# zeta2rework_lw_v20.net
KiCad netlist of a schematic drawn in EAGLE
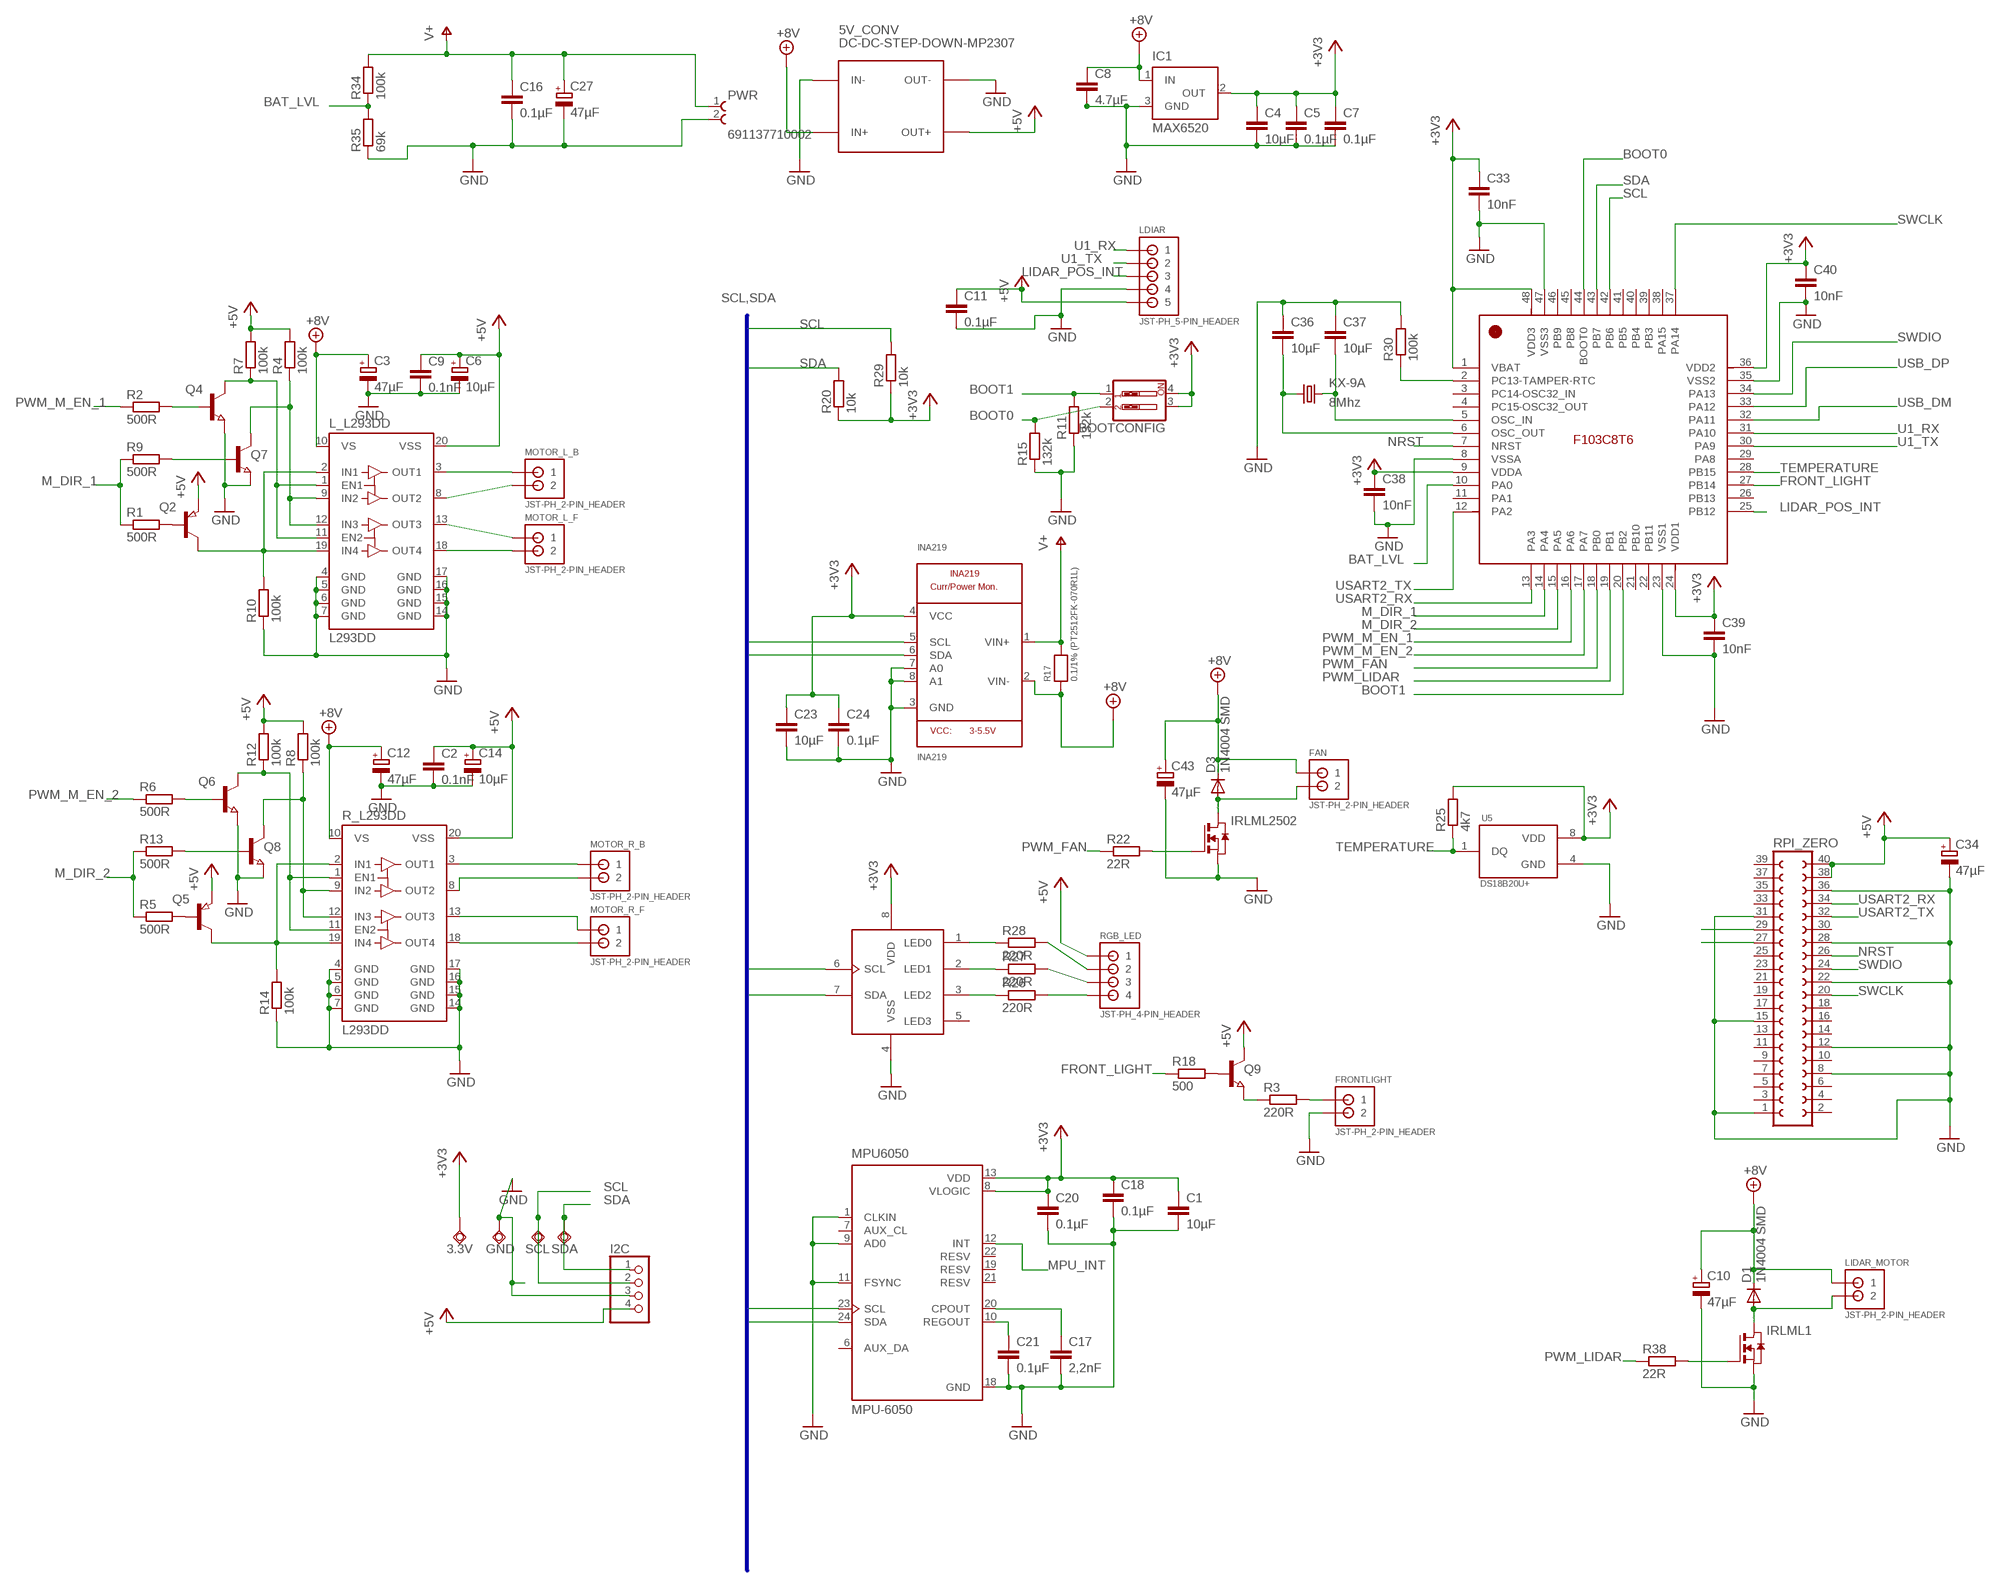
[diagram p0: schematic, sheet 1]

(export (version "E")
  (design (tool "Eeschema 10.0.6"))
  (components
    (comp (ref "3.3V")
      (value "TPSQTP20R")
      (footprint "eagle-import:TP20R")
      (libsource (lib "eagle-import") (part "TPSQTP20R"))
    )
    (comp (ref "5V_CONV")
      (value "DC-DC-STEP-DOWN-MP2307")
      (footprint "eagle-import:DC-DC-STEP-DOWN-MP2307")
      (libsource (lib "eagle-import") (part "DC-DC-STEP-DOWN-MP2307"))
    )
    (comp (ref "BOOTCONFIG")
      (value "SW_DIP-2")
      (footprint "eagle-import:EDG-02")
      (libsource (lib "eagle-import") (part "SW_DIP-2"))
    )
    (comp (ref "C1")
      (value "10µF")
      (footprint "eagle-import:C1206")
      (libsource (lib "eagle-import") (part "C-EUC1206"))
    )
    (comp (ref "C2")
      (value "0.1nF")
      (footprint "eagle-import:C1206")
      (libsource (lib "eagle-import") (part "C-EUC1206"))
    )
    (comp (ref "C3")
      (value "47µF")
      (footprint "eagle-import:UD-4X5,8_NICHICON")
      (libsource (lib "eagle-import") (part "CPOL-EUUD-4X5,8"))
    )
    (comp (ref "C4")
      (value "10µF")
      (footprint "eagle-import:C1206")
      (libsource (lib "eagle-import") (part "C-EUC1206"))
    )
    (comp (ref "C5")
      (value "0.1µF")
      (footprint "eagle-import:C1206")
      (libsource (lib "eagle-import") (part "C-EUC1206"))
    )
    (comp (ref "C6")
      (value "10µF")
      (footprint "eagle-import:UD-4X5,8_NICHICON")
      (libsource (lib "eagle-import") (part "CPOL-EUUD-4X5,8"))
    )
    (comp (ref "C7")
      (value "0.1µF")
      (footprint "eagle-import:C1206")
      (libsource (lib "eagle-import") (part "C-EUC1206"))
    )
    (comp (ref "C8")
      (value "4.7µF")
      (footprint "eagle-import:C1206")
      (libsource (lib "eagle-import") (part "C-EUC1206"))
    )
    (comp (ref "C9")
      (value "0.1nF")
      (footprint "eagle-import:C1206")
      (libsource (lib "eagle-import") (part "C-EUC1206"))
    )
    (comp (ref "C10")
      (value "47µF")
      (footprint "eagle-import:UD-4X5,8_NICHICON")
      (libsource (lib "eagle-import") (part "CPOL-EUUD-4X5,8"))
    )
    (comp (ref "C11")
      (value "0.1µF")
      (footprint "eagle-import:C1206")
      (libsource (lib "eagle-import") (part "C-EUC1206"))
    )
    (comp (ref "C12")
      (value "47µF")
      (footprint "eagle-import:UD-4X5,8_NICHICON")
      (libsource (lib "eagle-import") (part "CPOL-EUUD-4X5,8"))
    )
    (comp (ref "C14")
      (value "10µF")
      (footprint "eagle-import:UD-4X5,8_NICHICON")
      (libsource (lib "eagle-import") (part "CPOL-EUUD-4X5,8"))
    )
    (comp (ref "C16")
      (value "0.1µF")
      (footprint "eagle-import:C1206")
      (libsource (lib "eagle-import") (part "C-EUC1206"))
    )
    (comp (ref "C17")
      (value "2,2nF")
      (footprint "eagle-import:C1206")
      (libsource (lib "eagle-import") (part "C-EUC1206"))
    )
    (comp (ref "C18")
      (value "0.1µF")
      (footprint "eagle-import:C1206")
      (libsource (lib "eagle-import") (part "C-EUC1206"))
    )
    (comp (ref "C20")
      (value "0.1µF")
      (footprint "eagle-import:C1206")
      (libsource (lib "eagle-import") (part "C-EUC1206"))
    )
    (comp (ref "C21")
      (value "0.1µF")
      (footprint "eagle-import:C1206")
      (libsource (lib "eagle-import") (part "C-EUC1206"))
    )
    (comp (ref "C23")
      (value "10µF")
      (footprint "eagle-import:C1206")
      (libsource (lib "eagle-import") (part "C-EUC1206"))
    )
    (comp (ref "C24")
      (value "0.1µF")
      (footprint "eagle-import:C1206")
      (libsource (lib "eagle-import") (part "C-EUC1206"))
    )
    (comp (ref "C27")
      (value "47µF")
      (footprint "eagle-import:UD-4X5,8_NICHICON")
      (libsource (lib "eagle-import") (part "CPOL-EUUD-4X5,8"))
    )
    (comp (ref "C33")
      (value "10nF")
      (footprint "eagle-import:C1206")
      (libsource (lib "eagle-import") (part "C-EUC1206"))
    )
    (comp (ref "C34")
      (value "47µF")
      (footprint "eagle-import:UD-4X5,8_NICHICON")
      (libsource (lib "eagle-import") (part "CPOL-EUUD-4X5,8"))
    )
    (comp (ref "C36")
      (value "10µF")
      (footprint "eagle-import:C1206")
      (libsource (lib "eagle-import") (part "C-EUC1206"))
    )
    (comp (ref "C37")
      (value "10µF")
      (footprint "eagle-import:C1206")
      (libsource (lib "eagle-import") (part "C-EUC1206"))
    )
    (comp (ref "C38")
      (value "10nF")
      (footprint "eagle-import:C1206")
      (libsource (lib "eagle-import") (part "C-EUC1206"))
    )
    (comp (ref "C39")
      (value "10nF")
      (footprint "eagle-import:C1206")
      (libsource (lib "eagle-import") (part "C-EUC1206"))
    )
    (comp (ref "C40")
      (value "10nF")
      (footprint "eagle-import:C1206")
      (libsource (lib "eagle-import") (part "C-EUC1206"))
    )
    (comp (ref "C43")
      (value "47µF")
      (footprint "eagle-import:UD-4X5,8_NICHICON")
      (libsource (lib "eagle-import") (part "CPOL-EUUD-4X5,8"))
    )
    (comp (ref "D1")
      (value "1N4004 SMD")
      (footprint "eagle-import:DO214AC")
      (libsource (lib "eagle-import") (part "DIODE-DO214AC"))
    )
    (comp (ref "D3")
      (value "1N4004 SMD")
      (footprint "eagle-import:DO214AC")
      (libsource (lib "eagle-import") (part "DIODE-DO214AC"))
    )
    (comp (ref "FAN")
      (value "JST-PH_2-PIN_HEADER")
      (footprint "eagle-import:JST_B2B-PH_HEADER")
      (libsource (lib "eagle-import") (part "JST-PH_2-PIN_HEADER"))
    )
    (comp (ref "FRONTLIGHT")
      (value "JST-PH_2-PIN_HEADER")
      (footprint "eagle-import:JST_B2B-PH_HEADER")
      (libsource (lib "eagle-import") (part "JST-PH_2-PIN_HEADER"))
    )
    (comp (ref "GND")
      (value "TPSQTP20R")
      (footprint "eagle-import:TP20R")
      (libsource (lib "eagle-import") (part "TPSQTP20R"))
    )
    (comp (ref "I2C")
      (value "PINHD-1X4")
      (footprint "eagle-import:1X04")
      (libsource (lib "eagle-import") (part "PINHD-1X4"))
    )
    (comp (ref "IC1")
      (value "MAX6520")
      (footprint "eagle-import:SOT23")
      (fields (field (name "MF") "MAXIM") (field (name "MPN") "MAX6520EUR-T"))
      (libsource (lib "eagle-import") (part "MAX6520"))
    )
    (comp (ref "INA219")
      (value "INA219")
      (footprint "eagle-import:SOT23-8")
      (fields (field (name "MF") "Texas Instruments"))
      (libsource (lib "eagle-import") (part "INA219"))
    )
    (comp (ref "IRLML1")
      (value "NMOSSOT23")
      (footprint "eagle-import:SOT-23")
      (libsource (lib "eagle-import") (part "NMOSSOT23"))
    )
    (comp (ref "IRLML2502")
      (value "NMOSSOT23")
      (footprint "eagle-import:SOT-23")
      (libsource (lib "eagle-import") (part "NMOSSOT23"))
    )
    (comp (ref "KX-9A")
      (value "8Mhz")
      (footprint "eagle-import:5.0X3.2_KX-9A")
      (libsource (lib "eagle-import") (part "KX-9A"))
    )
    (comp (ref "LDIAR")
      (value "JST-PH_5-PIN_HEADER")
      (footprint "eagle-import:JST_B5B-PH_HEADER")
      (libsource (lib "eagle-import") (part "JST-PH_5-PIN_HEADER"))
    )
    (comp (ref "LIDAR_MOTOR")
      (value "JST-PH_2-PIN_HEADER")
      (footprint "eagle-import:JST_B2B-PH_HEADER")
      (libsource (lib "eagle-import") (part "JST-PH_2-PIN_HEADER"))
    )
    (comp (ref "L_L293DD")
      (value "L293DD")
      (footprint "eagle-import:SO20")
      (libsource (lib "eagle-import") (part "L293DD"))
    )
    (comp (ref "MOTOR_L_B")
      (value "JST-PH_2-PIN_HEADER")
      (footprint "eagle-import:JST_B2B-PH_HEADER")
      (libsource (lib "eagle-import") (part "JST-PH_2-PIN_HEADER"))
    )
    (comp (ref "MOTOR_L_F")
      (value "JST-PH_2-PIN_HEADER")
      (footprint "eagle-import:JST_B2B-PH_HEADER")
      (libsource (lib "eagle-import") (part "JST-PH_2-PIN_HEADER"))
    )
    (comp (ref "MOTOR_R_B")
      (value "JST-PH_2-PIN_HEADER")
      (footprint "eagle-import:JST_B2B-PH_HEADER")
      (libsource (lib "eagle-import") (part "JST-PH_2-PIN_HEADER"))
    )
    (comp (ref "MOTOR_R_F")
      (value "JST-PH_2-PIN_HEADER")
      (footprint "eagle-import:JST_B2B-PH_HEADER")
      (libsource (lib "eagle-import") (part "JST-PH_2-PIN_HEADER"))
    )
    (comp (ref "MPU6050")
      (value "MPU-6050")
      (footprint "eagle-import:QFN50P400X400X95-24N")
      (fields (field (name "MF") "TDK"))
      (libsource (lib "eagle-import") (part "MPU-6050"))
    )
    (comp (ref "PCA9533")
      (value "PCA9533")
      (footprint "eagle-import:SOIC8")
      (libsource (lib "eagle-import") (part "PCA9533"))
    )
    (comp (ref "PWR")
      (value "691137710002")
      (footprint "eagle-import:691137710002")
      (fields (field (name "MF") "Wurth Electronics"))
      (libsource (lib "eagle-import") (part "691137710002"))
    )
    (comp (ref "Q2")
      (value "PNP-TRANSISTOR_SOT23")
      (footprint "eagle-import:SOT23")
      (libsource (lib "eagle-import") (part "PNP-TRANSISTOR_SOT23"))
    )
    (comp (ref "Q4")
      (value "NPN-TRANSISTOR_SOT23")
      (footprint "eagle-import:SOT23")
      (libsource (lib "eagle-import") (part "NPN-TRANSISTOR_SOT23"))
    )
    (comp (ref "Q5")
      (value "PNP-TRANSISTOR_SOT23")
      (footprint "eagle-import:SOT23")
      (libsource (lib "eagle-import") (part "PNP-TRANSISTOR_SOT23"))
    )
    (comp (ref "Q6")
      (value "NPN-TRANSISTOR_SOT23")
      (footprint "eagle-import:SOT23")
      (libsource (lib "eagle-import") (part "NPN-TRANSISTOR_SOT23"))
    )
    (comp (ref "Q7")
      (value "NPN-TRANSISTOR_SOT23")
      (footprint "eagle-import:SOT23")
      (libsource (lib "eagle-import") (part "NPN-TRANSISTOR_SOT23"))
    )
    (comp (ref "Q8")
      (value "NPN-TRANSISTOR_SOT23")
      (footprint "eagle-import:SOT23")
      (libsource (lib "eagle-import") (part "NPN-TRANSISTOR_SOT23"))
    )
    (comp (ref "Q9")
      (value "NPN-TRANSISTOR_SOT23")
      (footprint "eagle-import:SOT23")
      (libsource (lib "eagle-import") (part "NPN-TRANSISTOR_SOT23"))
    )
    (comp (ref "R1")
      (value "500R")
      (footprint "eagle-import:R0603")
      (libsource (lib "eagle-import") (part "R-EU_R0603"))
    )
    (comp (ref "R2")
      (value "500R")
      (footprint "eagle-import:R0603")
      (libsource (lib "eagle-import") (part "R-EU_R0603"))
    )
    (comp (ref "R3")
      (value "220R")
      (footprint "eagle-import:R0603")
      (libsource (lib "eagle-import") (part "R-EU_R0603"))
    )
    (comp (ref "R4")
      (value "100k")
      (footprint "eagle-import:R0603")
      (libsource (lib "eagle-import") (part "R-EU_R0603"))
    )
    (comp (ref "R5")
      (value "500R")
      (footprint "eagle-import:R0603")
      (libsource (lib "eagle-import") (part "R-EU_R0603"))
    )
    (comp (ref "R6")
      (value "500R")
      (footprint "eagle-import:R0603")
      (libsource (lib "eagle-import") (part "R-EU_R0603"))
    )
    (comp (ref "R7")
      (value "100k")
      (footprint "eagle-import:R0603")
      (libsource (lib "eagle-import") (part "R-EU_R0603"))
    )
    (comp (ref "R8")
      (value "100k")
      (footprint "eagle-import:R0603")
      (libsource (lib "eagle-import") (part "R-EU_R0603"))
    )
    (comp (ref "R9")
      (value "500R")
      (footprint "eagle-import:R0603")
      (libsource (lib "eagle-import") (part "R-EU_R0603"))
    )
    (comp (ref "R10")
      (value "100k")
      (footprint "eagle-import:R0603")
      (libsource (lib "eagle-import") (part "R-EU_R0603"))
    )
    (comp (ref "R11")
      (value "132k")
      (footprint "eagle-import:R0603")
      (libsource (lib "eagle-import") (part "R-EU_R0603"))
    )
    (comp (ref "R12")
      (value "100k")
      (footprint "eagle-import:R0603")
      (libsource (lib "eagle-import") (part "R-EU_R0603"))
    )
    (comp (ref "R13")
      (value "500R")
      (footprint "eagle-import:R0603")
      (libsource (lib "eagle-import") (part "R-EU_R0603"))
    )
    (comp (ref "R14")
      (value "100k")
      (footprint "eagle-import:R0603")
      (libsource (lib "eagle-import") (part "R-EU_R0603"))
    )
    (comp (ref "R15")
      (value "132k")
      (footprint "eagle-import:R0603")
      (libsource (lib "eagle-import") (part "R-EU_R0603"))
    )
    (comp (ref "R17")
      (value "0.1/1% (PT2512FK-070R1L)")
      (footprint "eagle-import:2512")
      (libsource (lib "eagle-import") (part "RESISTOR2512"))
    )
    (comp (ref "R18")
      (value "500")
      (footprint "eagle-import:R0603")
      (libsource (lib "eagle-import") (part "R-EU_R0603"))
    )
    (comp (ref "R20")
      (value "10k")
      (footprint "eagle-import:R0603")
      (libsource (lib "eagle-import") (part "R-EU_R0603"))
    )
    (comp (ref "R22")
      (value "22R")
      (footprint "eagle-import:R0603")
      (libsource (lib "eagle-import") (part "R-EU_R0603"))
    )
    (comp (ref "R25")
      (value "4k7")
      (footprint "eagle-import:R0603")
      (libsource (lib "eagle-import") (part "R-EU_R0603"))
    )
    (comp (ref "R26")
      (value "220R")
      (footprint "eagle-import:R0603")
      (libsource (lib "eagle-import") (part "R-EU_R0603"))
    )
    (comp (ref "R27")
      (value "220R")
      (footprint "eagle-import:R0603")
      (libsource (lib "eagle-import") (part "R-EU_R0603"))
    )
    (comp (ref "R28")
      (value "220R")
      (footprint "eagle-import:R0603")
      (libsource (lib "eagle-import") (part "R-EU_R0603"))
    )
    (comp (ref "R29")
      (value "10k")
      (footprint "eagle-import:R0603")
      (libsource (lib "eagle-import") (part "R-EU_R0603"))
    )
    (comp (ref "R30")
      (value "100k")
      (footprint "eagle-import:R0603")
      (libsource (lib "eagle-import") (part "R-EU_R0603"))
    )
    (comp (ref "R34")
      (value "100k")
      (footprint "eagle-import:R0603")
      (libsource (lib "eagle-import") (part "R-EU_R0603"))
    )
    (comp (ref "R35")
      (value "69k")
      (footprint "eagle-import:R0603")
      (libsource (lib "eagle-import") (part "R-EU_R0603"))
    )
    (comp (ref "R38")
      (value "22R")
      (footprint "eagle-import:R0603")
      (libsource (lib "eagle-import") (part "R-EU_R0603"))
    )
    (comp (ref "RGB_LED")
      (value "JST-PH_4-PIN_HEADER")
      (footprint "eagle-import:JST_B4B-PH_HEADER")
      (libsource (lib "eagle-import") (part "JST-PH_4-PIN_HEADER"))
    )
    (comp (ref "RPI_ZERO")
      (value "FE20-2")
      (footprint "eagle-import:FE20-2")
      (libsource (lib "eagle-import") (part "FE20-2"))
    )
    (comp (ref "R_L293DD")
      (value "L293DD")
      (footprint "eagle-import:SO20")
      (libsource (lib "eagle-import") (part "L293DD"))
    )
    (comp (ref "SCL")
      (value "TPSQTP20R")
      (footprint "eagle-import:TP20R")
      (libsource (lib "eagle-import") (part "TPSQTP20R"))
    )
    (comp (ref "SDA")
      (value "TPSQTP20R")
      (footprint "eagle-import:TP20R")
      (libsource (lib "eagle-import") (part "TPSQTP20R"))
    )
    (comp (ref "STM32F103CB")
      (value "STM32F103CB")
      (footprint "eagle-import:LQFP48_7X7MM_0.5MMPP")
      (fields (field (name "MF") "STMicroelectronics") (field (name "MP") "STM32F103C8T6"))
      (libsource (lib "eagle-import") (part "STM32F103C8T6"))
    )
    (comp (ref "U5")
      (value "DS18B20U+")
      (footprint "eagle-import:SOP65P490X95-8N")
      (fields (field (name "MF") "Maxim"))
      (libsource (lib "eagle-import") (part "DS18B20U+"))
    )
  )
  (nets
    (net (code "1") (name "+3V3") (class "Default")
      (node (ref "3.3V") (pin "TP") (pinfunction "TP_TP") (pintype "input"))
      (node (ref "BOOTCONFIG") (pin "3") (pinfunction "3_3") (pintype "passive"))
      (node (ref "BOOTCONFIG") (pin "4") (pinfunction "4_4") (pintype "passive"))
      (node (ref "C1") (pin "1") (pinfunction "1_1") (pintype "passive"))
      (node (ref "C18") (pin "1") (pinfunction "1_1") (pintype "passive"))
      (node (ref "C20") (pin "1") (pinfunction "1_1") (pintype "passive"))
      (node (ref "C23") (pin "1") (pinfunction "1_1") (pintype "passive"))
      (node (ref "C24") (pin "1") (pinfunction "1_1") (pintype "passive"))
      (node (ref "C33") (pin "1") (pinfunction "1_1") (pintype "passive"))
      (node (ref "C38") (pin "1") (pinfunction "1_1") (pintype "passive"))
      (node (ref "C39") (pin "1") (pinfunction "1_1") (pintype "passive"))
      (node (ref "C4") (pin "1") (pinfunction "1_1") (pintype "passive"))
      (node (ref "C40") (pin "1") (pinfunction "1_1") (pintype "passive"))
      (node (ref "C5") (pin "1") (pinfunction "1_1") (pintype "passive"))
      (node (ref "C7") (pin "1") (pinfunction "1_1") (pintype "passive"))
      (node (ref "IC1") (pin "2") (pinfunction "OUT_2") (pintype "output"))
      (node (ref "INA219") (pin "4") (pinfunction "VCC_4") (pintype "bidirectional"))
      (node (ref "MPU6050") (pin "13") (pinfunction "VDD_13") (pintype "power_in"))
      (node (ref "MPU6050") (pin "8") (pinfunction "VLOGIC_8") (pintype "power_in"))
      (node (ref "PCA9533") (pin "8") (pinfunction "VDD_8") (pintype "power_in"))
      (node (ref "R20") (pin "1") (pinfunction "1_1") (pintype "passive"))
      (node (ref "R25") (pin "2") (pinfunction "2_2") (pintype "passive"))
      (node (ref "R29") (pin "1") (pinfunction "1_1") (pintype "passive"))
      (node (ref "STM32F103CB") (pin "1") (pinfunction "VBAT_1") (pintype "bidirectional"))
      (node (ref "STM32F103CB") (pin "24") (pinfunction "VDD1_24") (pintype "bidirectional"))
      (node (ref "STM32F103CB") (pin "36") (pinfunction "VDD2_36") (pintype "bidirectional"))
      (node (ref "STM32F103CB") (pin "48") (pinfunction "VDD3_48") (pintype "bidirectional"))
      (node (ref "STM32F103CB") (pin "9") (pinfunction "VDDA_9") (pintype "bidirectional"))
      (node (ref "U5") (pin "8") (pinfunction "VDD_8") (pintype "power_in"))
    )
    (net (code "2") (name "+5V") (class "Default")
      (node (ref "5V_CONV") (pin "OUT+") (pinfunction "OUT+_OUT+") (pintype "bidirectional"))
      (node (ref "C11") (pin "1") (pinfunction "1_1") (pintype "passive"))
      (node (ref "C14") (pin "+") (pinfunction "+_+") (pintype "passive"))
      (node (ref "C2") (pin "1") (pinfunction "1_1") (pintype "passive"))
      (node (ref "C34") (pin "+") (pinfunction "+_+") (pintype "passive"))
      (node (ref "C6") (pin "+") (pinfunction "+_+") (pintype "passive"))
      (node (ref "C9") (pin "1") (pinfunction "1_1") (pintype "passive"))
      (node (ref "I2C") (pin "4") (pinfunction "4_4") (pintype "passive"))
      (node (ref "LDIAR") (pin "P5") (pinfunction "5_P5") (pintype "bidirectional"))
      (node (ref "L_L293DD") (pin "20") (pinfunction "VSS_20") (pintype "power_in"))
      (node (ref "Q2") (pin "2") (pinfunction "E_2") (pintype "passive"))
      (node (ref "Q5") (pin "2") (pinfunction "E_2") (pintype "passive"))
      (node (ref "Q9") (pin "3") (pinfunction "C_3") (pintype "passive"))
      (node (ref "R12") (pin "2") (pinfunction "2_2") (pintype "passive"))
      (node (ref "R4") (pin "2") (pinfunction "2_2") (pintype "passive"))
      (node (ref "R7") (pin "2") (pinfunction "2_2") (pintype "passive"))
      (node (ref "R8") (pin "2") (pinfunction "2_2") (pintype "passive"))
      (node (ref "RGB_LED") (pin "P1") (pinfunction "1_P1") (pintype "bidirectional"))
      (node (ref "RPI_ZERO") (pin "38") (pinfunction "38_38") (pintype "passive"))
      (node (ref "RPI_ZERO") (pin "40") (pinfunction "40_40") (pintype "passive"))
      (node (ref "R_L293DD") (pin "20") (pinfunction "VSS_20") (pintype "power_in"))
    )
    (net (code "3") (name "+8V") (class "Default")
      (node (ref "5V_CONV") (pin "IN+") (pinfunction "IN+_IN+") (pintype "bidirectional"))
      (node (ref "C10") (pin "+") (pinfunction "+_+") (pintype "passive"))
      (node (ref "C12") (pin "+") (pinfunction "+_+") (pintype "passive"))
      (node (ref "C3") (pin "+") (pinfunction "+_+") (pintype "passive"))
      (node (ref "C43") (pin "+") (pinfunction "+_+") (pintype "passive"))
      (node (ref "C8") (pin "1") (pinfunction "1_1") (pintype "passive"))
      (node (ref "D1") (pin "C") (pinfunction "C_C") (pintype "passive"))
      (node (ref "D3") (pin "C") (pinfunction "C_C") (pintype "passive"))
      (node (ref "FAN") (pin "P1") (pinfunction "1_P1") (pintype "bidirectional"))
      (node (ref "IC1") (pin "1") (pinfunction "IN_1") (pintype "input"))
      (node (ref "INA219") (pin "2") (pinfunction "VIN-_2") (pintype "bidirectional"))
      (node (ref "LIDAR_MOTOR") (pin "P1") (pinfunction "1_P1") (pintype "bidirectional"))
      (node (ref "L_L293DD") (pin "10") (pinfunction "VS_10") (pintype "power_in"))
      (node (ref "R17") (pin "1") (pinfunction "1_1") (pintype "passive"))
      (node (ref "R_L293DD") (pin "10") (pinfunction "VS_10") (pintype "power_in"))
    )
    (net (code "4") (name "/BAT_LVL") (class "Default")
      (node (ref "R34") (pin "1") (pinfunction "1_1") (pintype "passive"))
      (node (ref "R35") (pin "2") (pinfunction "2_2") (pintype "passive"))
      (node (ref "STM32F103CB") (pin "10") (pinfunction "PA0_10") (pintype "bidirectional"))
    )
    (net (code "5") (name "/BOOT0") (class "Default")
      (node (ref "BOOTCONFIG") (pin "2") (pinfunction "2_2") (pintype "passive"))
      (node (ref "R15") (pin "2") (pinfunction "2_2") (pintype "passive"))
      (node (ref "STM32F103CB") (pin "44") (pinfunction "BOOT0_44") (pintype "bidirectional"))
    )
    (net (code "6") (name "/BOOT1") (class "Default")
      (node (ref "BOOTCONFIG") (pin "1") (pinfunction "1_1") (pintype "passive"))
      (node (ref "R11") (pin "2") (pinfunction "2_2") (pintype "passive"))
      (node (ref "STM32F103CB") (pin "20") (pinfunction "PB2_20") (pintype "bidirectional"))
    )
    (net (code "7") (name "/FRONT_LIGHT") (class "Default")
      (node (ref "R18") (pin "1") (pinfunction "1_1") (pintype "passive"))
      (node (ref "STM32F103CB") (pin "27") (pinfunction "PB14_27") (pintype "bidirectional"))
    )
    (net (code "8") (name "/LIDAR_POS_INT") (class "Default")
      (node (ref "LDIAR") (pin "P3") (pinfunction "3_P3") (pintype "bidirectional"))
      (node (ref "STM32F103CB") (pin "25") (pinfunction "PB12_25") (pintype "bidirectional"))
    )
    (net (code "9") (name "/MPU_INT") (class "Default")
      (node (ref "MPU6050") (pin "12") (pinfunction "INT_12") (pintype "output"))
    )
    (net (code "10") (name "/M_DIR_1") (class "Default")
      (node (ref "R1") (pin "1") (pinfunction "1_1") (pintype "passive"))
      (node (ref "R9") (pin "1") (pinfunction "1_1") (pintype "passive"))
      (node (ref "STM32F103CB") (pin "14") (pinfunction "PA4_14") (pintype "bidirectional"))
    )
    (net (code "11") (name "/M_DIR_2") (class "Default")
      (node (ref "R13") (pin "1") (pinfunction "1_1") (pintype "passive"))
      (node (ref "R5") (pin "1") (pinfunction "1_1") (pintype "passive"))
      (node (ref "STM32F103CB") (pin "15") (pinfunction "PA5_15") (pintype "bidirectional"))
    )
    (net (code "12") (name "/NRST") (class "Default")
      (node (ref "RPI_ZERO") (pin "26") (pinfunction "26_26") (pintype "passive"))
      (node (ref "STM32F103CB") (pin "7") (pinfunction "NRST_7") (pintype "bidirectional"))
    )
    (net (code "13") (name "/PWM_FAN") (class "Default")
      (node (ref "R22") (pin "1") (pinfunction "1_1") (pintype "passive"))
      (node (ref "STM32F103CB") (pin "18") (pinfunction "PB0_18") (pintype "bidirectional"))
    )
    (net (code "14") (name "/PWM_LIDAR") (class "Default")
      (node (ref "R38") (pin "1") (pinfunction "1_1") (pintype "passive"))
      (node (ref "STM32F103CB") (pin "19") (pinfunction "PB1_19") (pintype "bidirectional"))
    )
    (net (code "15") (name "/PWM_M_EN_1") (class "Default")
      (node (ref "R2") (pin "1") (pinfunction "1_1") (pintype "passive"))
      (node (ref "STM32F103CB") (pin "16") (pinfunction "PA6_16") (pintype "bidirectional"))
    )
    (net (code "16") (name "/PWM_M_EN_2") (class "Default")
      (node (ref "R6") (pin "1") (pinfunction "1_1") (pintype "passive"))
      (node (ref "STM32F103CB") (pin "17") (pinfunction "PA7_17") (pintype "bidirectional"))
    )
    (net (code "17") (name "/SCL") (class "Default")
      (node (ref "I2C") (pin "2") (pinfunction "2_2") (pintype "passive"))
      (node (ref "INA219") (pin "5") (pinfunction "SCL_5") (pintype "bidirectional"))
      (node (ref "MPU6050") (pin "23") (pinfunction "SCL_23") (pintype "input"))
      (node (ref "PCA9533") (pin "6") (pinfunction "SCL_6") (pintype "input"))
      (node (ref "R29") (pin "2") (pinfunction "2_2") (pintype "passive"))
      (node (ref "SCL") (pin "TP") (pinfunction "TP_TP") (pintype "input"))
      (node (ref "STM32F103CB") (pin "42") (pinfunction "PB6_42") (pintype "bidirectional"))
    )
    (net (code "18") (name "/SDA") (class "Default")
      (node (ref "I2C") (pin "1") (pinfunction "1_1") (pintype "passive"))
      (node (ref "INA219") (pin "6") (pinfunction "SDA_6") (pintype "bidirectional"))
      (node (ref "MPU6050") (pin "24") (pinfunction "SDA_24") (pintype "bidirectional"))
      (node (ref "PCA9533") (pin "7") (pinfunction "SDA_7") (pintype "bidirectional"))
      (node (ref "R20") (pin "2") (pinfunction "2_2") (pintype "passive"))
      (node (ref "SDA") (pin "TP") (pinfunction "TP_TP") (pintype "input"))
      (node (ref "STM32F103CB") (pin "43") (pinfunction "PB7_43") (pintype "bidirectional"))
    )
    (net (code "19") (name "/SWCLK") (class "Default")
      (node (ref "RPI_ZERO") (pin "20") (pinfunction "20_20") (pintype "passive"))
      (node (ref "STM32F103CB") (pin "37") (pinfunction "PA14_37") (pintype "bidirectional"))
    )
    (net (code "20") (name "/SWDIO") (class "Default")
      (node (ref "RPI_ZERO") (pin "24") (pinfunction "24_24") (pintype "passive"))
      (node (ref "STM32F103CB") (pin "34") (pinfunction "PA13_34") (pintype "bidirectional"))
    )
    (net (code "21") (name "/TEMPERATURE") (class "Default")
      (node (ref "R25") (pin "1") (pinfunction "1_1") (pintype "passive"))
      (node (ref "STM32F103CB") (pin "28") (pinfunction "PB15_28") (pintype "bidirectional"))
      (node (ref "U5") (pin "1") (pinfunction "DQ_1") (pintype "bidirectional"))
    )
    (net (code "22") (name "/U1_RX") (class "Default")
      (node (ref "LDIAR") (pin "P1") (pinfunction "1_P1") (pintype "bidirectional"))
      (node (ref "STM32F103CB") (pin "31") (pinfunction "PA10_31") (pintype "bidirectional"))
    )
    (net (code "23") (name "/U1_TX") (class "Default")
      (node (ref "LDIAR") (pin "P2") (pinfunction "2_P2") (pintype "bidirectional"))
      (node (ref "STM32F103CB") (pin "30") (pinfunction "PA9_30") (pintype "bidirectional"))
    )
    (net (code "24") (name "/USART2_RX") (class "Default")
      (node (ref "RPI_ZERO") (pin "34") (pinfunction "34_34") (pintype "passive"))
      (node (ref "STM32F103CB") (pin "13") (pinfunction "PA3_13") (pintype "bidirectional"))
    )
    (net (code "25") (name "/USART2_TX") (class "Default")
      (node (ref "RPI_ZERO") (pin "32") (pinfunction "32_32") (pintype "passive"))
      (node (ref "STM32F103CB") (pin "12") (pinfunction "PA2_12") (pintype "bidirectional"))
    )
    (net (code "26") (name "/USB_DM") (class "Default")
      (node (ref "STM32F103CB") (pin "32") (pinfunction "PA11_32") (pintype "bidirectional"))
    )
    (net (code "27") (name "/USB_DP") (class "Default")
      (node (ref "STM32F103CB") (pin "33") (pinfunction "PA12_33") (pintype "bidirectional"))
    )
    (net (code "29") (name "GND") (class "Default")
      (node (ref "5V_CONV") (pin "IN-") (pinfunction "IN-_IN-") (pintype "bidirectional"))
      (node (ref "5V_CONV") (pin "OUT-") (pinfunction "OUT-_OUT-") (pintype "bidirectional"))
      (node (ref "C1") (pin "2") (pinfunction "2_2") (pintype "passive"))
      (node (ref "C10") (pin "-") (pinfunction "-_-") (pintype "passive"))
      (node (ref "C11") (pin "2") (pinfunction "2_2") (pintype "passive"))
      (node (ref "C12") (pin "-") (pinfunction "-_-") (pintype "passive"))
      (node (ref "C14") (pin "-") (pinfunction "-_-") (pintype "passive"))
      (node (ref "C16") (pin "2") (pinfunction "2_2") (pintype "passive"))
      (node (ref "C17") (pin "2") (pinfunction "2_2") (pintype "passive"))
      (node (ref "C18") (pin "2") (pinfunction "2_2") (pintype "passive"))
      (node (ref "C2") (pin "2") (pinfunction "2_2") (pintype "passive"))
      (node (ref "C20") (pin "2") (pinfunction "2_2") (pintype "passive"))
      (node (ref "C21") (pin "2") (pinfunction "2_2") (pintype "passive"))
      (node (ref "C23") (pin "2") (pinfunction "2_2") (pintype "passive"))
      (node (ref "C24") (pin "2") (pinfunction "2_2") (pintype "passive"))
      (node (ref "C27") (pin "-") (pinfunction "-_-") (pintype "passive"))
      (node (ref "C3") (pin "-") (pinfunction "-_-") (pintype "passive"))
      (node (ref "C33") (pin "2") (pinfunction "2_2") (pintype "passive"))
      (node (ref "C34") (pin "-") (pinfunction "-_-") (pintype "passive"))
      (node (ref "C36") (pin "1") (pinfunction "1_1") (pintype "passive"))
      (node (ref "C37") (pin "1") (pinfunction "1_1") (pintype "passive"))
      (node (ref "C38") (pin "2") (pinfunction "2_2") (pintype "passive"))
      (node (ref "C39") (pin "2") (pinfunction "2_2") (pintype "passive"))
      (node (ref "C4") (pin "2") (pinfunction "2_2") (pintype "passive"))
      (node (ref "C40") (pin "2") (pinfunction "2_2") (pintype "passive"))
      (node (ref "C43") (pin "-") (pinfunction "-_-") (pintype "passive"))
      (node (ref "C5") (pin "2") (pinfunction "2_2") (pintype "passive"))
      (node (ref "C6") (pin "-") (pinfunction "-_-") (pintype "passive"))
      (node (ref "C7") (pin "2") (pinfunction "2_2") (pintype "passive"))
      (node (ref "C8") (pin "2") (pinfunction "2_2") (pintype "passive"))
      (node (ref "C9") (pin "2") (pinfunction "2_2") (pintype "passive"))
      (node (ref "FRONTLIGHT") (pin "P2") (pinfunction "2_P2") (pintype "bidirectional"))
      (node (ref "GND") (pin "TP") (pinfunction "TP_TP") (pintype "input"))
      (node (ref "I2C") (pin "3") (pinfunction "3_3") (pintype "passive"))
      (node (ref "IC1") (pin "3") (pinfunction "GND_3") (pintype "power_in"))
      (node (ref "INA219") (pin "3") (pinfunction "GND_3") (pintype "bidirectional"))
      (node (ref "INA219") (pin "7") (pinfunction "A0_7") (pintype "bidirectional"))
      (node (ref "INA219") (pin "8") (pinfunction "A1_8") (pintype "bidirectional"))
      (node (ref "IRLML1") (pin "2") (pinfunction "S_2") (pintype "passive"))
      (node (ref "IRLML2502") (pin "2") (pinfunction "S_2") (pintype "passive"))
      (node (ref "LDIAR") (pin "P4") (pinfunction "4_P4") (pintype "bidirectional"))
      (node (ref "L_L293DD") (pin "14") (pinfunction "GND_14") (pintype "power_in"))
      (node (ref "L_L293DD") (pin "15") (pinfunction "GND_15") (pintype "power_in"))
      (node (ref "L_L293DD") (pin "16") (pinfunction "GND_16") (pintype "power_in"))
      (node (ref "L_L293DD") (pin "17") (pinfunction "GND_17") (pintype "power_in"))
      (node (ref "L_L293DD") (pin "4") (pinfunction "GND_4") (pintype "power_in"))
      (node (ref "L_L293DD") (pin "5") (pinfunction "GND_5") (pintype "power_in"))
      (node (ref "L_L293DD") (pin "6") (pinfunction "GND_6") (pintype "power_in"))
      (node (ref "L_L293DD") (pin "7") (pinfunction "GND_7") (pintype "power_in"))
      (node (ref "MPU6050") (pin "1") (pinfunction "CLKIN_1") (pintype "input"))
      (node (ref "MPU6050") (pin "11") (pinfunction "FSYNC_11") (pintype "input"))
      (node (ref "MPU6050") (pin "18") (pinfunction "GND_18") (pintype "power_in"))
      (node (ref "MPU6050") (pin "9") (pinfunction "AD0_9") (pintype "input"))
      (node (ref "PCA9533") (pin "4") (pinfunction "VSS_4") (pintype "power_in"))
      (node (ref "PWR") (pin "2") (pinfunction "2_2") (pintype "passive"))
      (node (ref "Q4") (pin "2") (pinfunction "E_2") (pintype "passive"))
      (node (ref "Q6") (pin "2") (pinfunction "E_2") (pintype "passive"))
      (node (ref "Q7") (pin "2") (pinfunction "E_2") (pintype "passive"))
      (node (ref "Q8") (pin "2") (pinfunction "E_2") (pintype "passive"))
      (node (ref "R10") (pin "1") (pinfunction "1_1") (pintype "passive"))
      (node (ref "R11") (pin "1") (pinfunction "1_1") (pintype "passive"))
      (node (ref "R14") (pin "1") (pinfunction "1_1") (pintype "passive"))
      (node (ref "R15") (pin "1") (pinfunction "1_1") (pintype "passive"))
      (node (ref "R30") (pin "2") (pinfunction "2_2") (pintype "passive"))
      (node (ref "R35") (pin "1") (pinfunction "1_1") (pintype "passive"))
      (node (ref "RPI_ZERO") (pin "1") (pinfunction "1_1") (pintype "passive"))
      (node (ref "RPI_ZERO") (pin "12") (pinfunction "12_12") (pintype "passive"))
      (node (ref "RPI_ZERO") (pin "15") (pinfunction "15_15") (pintype "passive"))
      (node (ref "RPI_ZERO") (pin "22") (pinfunction "22_22") (pintype "passive"))
      (node (ref "RPI_ZERO") (pin "28") (pinfunction "28_28") (pintype "passive"))
      (node (ref "RPI_ZERO") (pin "31") (pinfunction "31_31") (pintype "passive"))
      (node (ref "RPI_ZERO") (pin "36") (pinfunction "36_36") (pintype "passive"))
      (node (ref "RPI_ZERO") (pin "8") (pinfunction "8_8") (pintype "passive"))
      (node (ref "R_L293DD") (pin "14") (pinfunction "GND_14") (pintype "power_in"))
      (node (ref "R_L293DD") (pin "15") (pinfunction "GND_15") (pintype "power_in"))
      (node (ref "R_L293DD") (pin "16") (pinfunction "GND_16") (pintype "power_in"))
      (node (ref "R_L293DD") (pin "17") (pinfunction "GND_17") (pintype "power_in"))
      (node (ref "R_L293DD") (pin "4") (pinfunction "GND_4") (pintype "power_in"))
      (node (ref "R_L293DD") (pin "5") (pinfunction "GND_5") (pintype "power_in"))
      (node (ref "R_L293DD") (pin "6") (pinfunction "GND_6") (pintype "power_in"))
      (node (ref "R_L293DD") (pin "7") (pinfunction "GND_7") (pintype "power_in"))
      (node (ref "STM32F103CB") (pin "23") (pinfunction "VSS1_23") (pintype "bidirectional"))
      (node (ref "STM32F103CB") (pin "35") (pinfunction "VSS2_35") (pintype "bidirectional"))
      (node (ref "STM32F103CB") (pin "47") (pinfunction "VSS3_47") (pintype "bidirectional"))
      (node (ref "STM32F103CB") (pin "8") (pinfunction "VSSA_8") (pintype "bidirectional"))
      (node (ref "U5") (pin "4") (pinfunction "GND_4") (pintype "power_in"))
    )
    (net (code "30") (name "Net-(FAN-2)") (class "Default")
      (node (ref "D3") (pin "A") (pinfunction "A_A") (pintype "passive"))
      (node (ref "FAN") (pin "P2") (pinfunction "2_P2") (pintype "bidirectional"))
      (node (ref "IRLML2502") (pin "1") (pinfunction "D_1") (pintype "passive"))
    )
    (net (code "31") (name "Net-(FRONTLIGHT-1)") (class "Default")
      (node (ref "FRONTLIGHT") (pin "P1") (pinfunction "1_P1") (pintype "bidirectional"))
      (node (ref "R3") (pin "2") (pinfunction "2_2") (pintype "passive"))
    )
    (net (code "32") (name "Net-(IRLML1-D)") (class "Default")
      (node (ref "D1") (pin "A") (pinfunction "A_A") (pintype "passive"))
      (node (ref "IRLML1") (pin "1") (pinfunction "D_1") (pintype "passive"))
      (node (ref "LIDAR_MOTOR") (pin "P2") (pinfunction "2_P2") (pintype "bidirectional"))
    )
    (net (code "33") (name "Net-(IRLML1-G)") (class "Default")
      (node (ref "IRLML1") (pin "3") (pinfunction "G_3") (pintype "passive"))
      (node (ref "R38") (pin "2") (pinfunction "2_2") (pintype "passive"))
    )
    (net (code "34") (name "Net-(IRLML2502-G)") (class "Default")
      (node (ref "IRLML2502") (pin "3") (pinfunction "G_3") (pintype "passive"))
      (node (ref "R22") (pin "2") (pinfunction "2_2") (pintype "passive"))
    )
    (net (code "35") (name "Net-(KX-9A-2)") (class "Default")
      (node (ref "C37") (pin "2") (pinfunction "2_2") (pintype "passive"))
      (node (ref "KX-9A") (pin "3") (pinfunction "2_3") (pintype "passive"))
      (node (ref "STM32F103CB") (pin "5") (pinfunction "OSC_IN_5") (pintype "bidirectional"))
    )
    (net (code "36") (name "Net-(L_L293DD-EN1)") (class "Default")
      (node (ref "L_L293DD") (pin "1") (pinfunction "EN1_1") (pintype "input"))
      (node (ref "L_L293DD") (pin "11") (pinfunction "EN2_11") (pintype "input"))
      (node (ref "Q4") (pin "3") (pinfunction "C_3") (pintype "passive"))
      (node (ref "R7") (pin "1") (pinfunction "1_1") (pintype "passive"))
    )
    (net (code "37") (name "Net-(L_L293DD-IN1)") (class "Default")
      (node (ref "L_L293DD") (pin "19") (pinfunction "IN4_19") (pintype "input"))
      (node (ref "L_L293DD") (pin "2") (pinfunction "IN1_2") (pintype "input"))
      (node (ref "Q2") (pin "3") (pinfunction "C_3") (pintype "passive"))
      (node (ref "R10") (pin "2") (pinfunction "2_2") (pintype "passive"))
    )
    (net (code "38") (name "Net-(L_L293DD-IN2)") (class "Default")
      (node (ref "L_L293DD") (pin "12") (pinfunction "IN3_12") (pintype "input"))
      (node (ref "L_L293DD") (pin "9") (pinfunction "IN2_9") (pintype "input"))
      (node (ref "Q7") (pin "3") (pinfunction "C_3") (pintype "passive"))
      (node (ref "R4") (pin "1") (pinfunction "1_1") (pintype "passive"))
    )
    (net (code "39") (name "Net-(L_L293DD-OUT1)") (class "Default")
      (node (ref "L_L293DD") (pin "3") (pinfunction "OUT1_3") (pintype "output"))
      (node (ref "MOTOR_L_B") (pin "P1") (pinfunction "1_P1") (pintype "bidirectional"))
    )
    (net (code "40") (name "Net-(L_L293DD-OUT2)") (class "Default")
      (node (ref "L_L293DD") (pin "8") (pinfunction "OUT2_8") (pintype "output"))
      (node (ref "MOTOR_L_B") (pin "P2") (pinfunction "2_P2") (pintype "bidirectional"))
    )
    (net (code "41") (name "Net-(L_L293DD-OUT3)") (class "Default")
      (node (ref "L_L293DD") (pin "13") (pinfunction "OUT3_13") (pintype "output"))
      (node (ref "MOTOR_L_F") (pin "P1") (pinfunction "1_P1") (pintype "bidirectional"))
    )
    (net (code "42") (name "Net-(L_L293DD-OUT4)") (class "Default")
      (node (ref "L_L293DD") (pin "18") (pinfunction "OUT4_18") (pintype "output"))
      (node (ref "MOTOR_L_F") (pin "P2") (pinfunction "2_P2") (pintype "bidirectional"))
    )
    (net (code "43") (name "Net-(MOTOR_R_B-1)") (class "Default")
      (node (ref "MOTOR_R_B") (pin "P1") (pinfunction "1_P1") (pintype "bidirectional"))
      (node (ref "R_L293DD") (pin "3") (pinfunction "OUT1_3") (pintype "output"))
    )
    (net (code "44") (name "Net-(MOTOR_R_B-2)") (class "Default")
      (node (ref "MOTOR_R_B") (pin "P2") (pinfunction "2_P2") (pintype "bidirectional"))
      (node (ref "R_L293DD") (pin "8") (pinfunction "OUT2_8") (pintype "output"))
    )
    (net (code "45") (name "Net-(MOTOR_R_F-1)") (class "Default")
      (node (ref "MOTOR_R_F") (pin "P1") (pinfunction "1_P1") (pintype "bidirectional"))
      (node (ref "R_L293DD") (pin "13") (pinfunction "OUT3_13") (pintype "output"))
    )
    (net (code "46") (name "Net-(MOTOR_R_F-2)") (class "Default")
      (node (ref "MOTOR_R_F") (pin "P2") (pinfunction "2_P2") (pintype "bidirectional"))
      (node (ref "R_L293DD") (pin "18") (pinfunction "OUT4_18") (pintype "output"))
    )
    (net (code "47") (name "Net-(MPU6050-CPOUT)") (class "Default")
      (node (ref "C17") (pin "1") (pinfunction "1_1") (pintype "passive"))
      (node (ref "MPU6050") (pin "20") (pinfunction "CPOUT_20") (pintype "passive"))
    )
    (net (code "48") (name "Net-(MPU6050-REGOUT)") (class "Default")
      (node (ref "C21") (pin "1") (pinfunction "1_1") (pintype "passive"))
      (node (ref "MPU6050") (pin "10") (pinfunction "REGOUT_10") (pintype "passive"))
    )
    (net (code "49") (name "Net-(PCA9533-LED0)") (class "Default")
      (node (ref "PCA9533") (pin "1") (pinfunction "LED0_1") (pintype "bidirectional"))
      (node (ref "R28") (pin "1") (pinfunction "1_1") (pintype "passive"))
    )
    (net (code "50") (name "Net-(PCA9533-LED1)") (class "Default")
      (node (ref "PCA9533") (pin "2") (pinfunction "LED1_2") (pintype "bidirectional"))
      (node (ref "R27") (pin "1") (pinfunction "1_1") (pintype "passive"))
    )
    (net (code "51") (name "Net-(PCA9533-LED2)") (class "Default")
      (node (ref "PCA9533") (pin "3") (pinfunction "LED2_3") (pintype "bidirectional"))
      (node (ref "R26") (pin "1") (pinfunction "1_1") (pintype "passive"))
    )
    (net (code "52") (name "Net-(Q2-B)") (class "Default")
      (node (ref "Q2") (pin "1") (pinfunction "B_1") (pintype "passive"))
      (node (ref "R1") (pin "2") (pinfunction "2_2") (pintype "passive"))
    )
    (net (code "53") (name "Net-(Q4-B)") (class "Default")
      (node (ref "Q4") (pin "1") (pinfunction "B_1") (pintype "passive"))
      (node (ref "R2") (pin "2") (pinfunction "2_2") (pintype "passive"))
    )
    (net (code "54") (name "Net-(Q5-B)") (class "Default")
      (node (ref "Q5") (pin "1") (pinfunction "B_1") (pintype "passive"))
      (node (ref "R5") (pin "2") (pinfunction "2_2") (pintype "passive"))
    )
    (net (code "55") (name "Net-(Q5-C)") (class "Default")
      (node (ref "Q5") (pin "3") (pinfunction "C_3") (pintype "passive"))
      (node (ref "R14") (pin "2") (pinfunction "2_2") (pintype "passive"))
      (node (ref "R_L293DD") (pin "19") (pinfunction "IN4_19") (pintype "input"))
      (node (ref "R_L293DD") (pin "2") (pinfunction "IN1_2") (pintype "input"))
    )
    (net (code "56") (name "Net-(Q6-B)") (class "Default")
      (node (ref "Q6") (pin "1") (pinfunction "B_1") (pintype "passive"))
      (node (ref "R6") (pin "2") (pinfunction "2_2") (pintype "passive"))
    )
    (net (code "57") (name "Net-(Q6-C)") (class "Default")
      (node (ref "Q6") (pin "3") (pinfunction "C_3") (pintype "passive"))
      (node (ref "R12") (pin "1") (pinfunction "1_1") (pintype "passive"))
      (node (ref "R_L293DD") (pin "1") (pinfunction "EN1_1") (pintype "input"))
      (node (ref "R_L293DD") (pin "11") (pinfunction "EN2_11") (pintype "input"))
    )
    (net (code "58") (name "Net-(Q7-B)") (class "Default")
      (node (ref "Q7") (pin "1") (pinfunction "B_1") (pintype "passive"))
      (node (ref "R9") (pin "2") (pinfunction "2_2") (pintype "passive"))
    )
    (net (code "59") (name "Net-(Q8-B)") (class "Default")
      (node (ref "Q8") (pin "1") (pinfunction "B_1") (pintype "passive"))
      (node (ref "R13") (pin "2") (pinfunction "2_2") (pintype "passive"))
    )
    (net (code "60") (name "Net-(Q8-C)") (class "Default")
      (node (ref "Q8") (pin "3") (pinfunction "C_3") (pintype "passive"))
      (node (ref "R8") (pin "1") (pinfunction "1_1") (pintype "passive"))
      (node (ref "R_L293DD") (pin "12") (pinfunction "IN3_12") (pintype "input"))
      (node (ref "R_L293DD") (pin "9") (pinfunction "IN2_9") (pintype "input"))
    )
    (net (code "61") (name "Net-(Q9-B)") (class "Default")
      (node (ref "Q9") (pin "1") (pinfunction "B_1") (pintype "passive"))
      (node (ref "R18") (pin "2") (pinfunction "2_2") (pintype "passive"))
    )
    (net (code "62") (name "Net-(Q9-E)") (class "Default")
      (node (ref "Q9") (pin "2") (pinfunction "E_2") (pintype "passive"))
      (node (ref "R3") (pin "1") (pinfunction "1_1") (pintype "passive"))
    )
    (net (code "63") (name "Net-(RGB_LED-2)") (class "Default")
      (node (ref "R28") (pin "2") (pinfunction "2_2") (pintype "passive"))
      (node (ref "RGB_LED") (pin "P2") (pinfunction "2_P2") (pintype "bidirectional"))
    )
    (net (code "64") (name "Net-(RGB_LED-3)") (class "Default")
      (node (ref "R27") (pin "2") (pinfunction "2_2") (pintype "passive"))
      (node (ref "RGB_LED") (pin "P3") (pinfunction "3_P3") (pintype "bidirectional"))
    )
    (net (code "65") (name "Net-(RGB_LED-4)") (class "Default")
      (node (ref "R26") (pin "2") (pinfunction "2_2") (pintype "passive"))
      (node (ref "RGB_LED") (pin "P4") (pinfunction "4_P4") (pintype "bidirectional"))
    )
    (net (code "66") (name "Net-(STM32F103CB-OSC_OUT)") (class "Default")
      (node (ref "C36") (pin "2") (pinfunction "2_2") (pintype "passive"))
      (node (ref "KX-9A") (pin "1") (pinfunction "1_1") (pintype "passive"))
      (node (ref "STM32F103CB") (pin "6") (pinfunction "OSC_OUT_6") (pintype "bidirectional"))
    )
    (net (code "67") (name "Net-(STM32F103CB-PC13-TAMPER-RTC)") (class "Default")
      (node (ref "R30") (pin "1") (pinfunction "1_1") (pintype "passive"))
      (node (ref "STM32F103CB") (pin "2") (pinfunction "PC13-TAMPER-RTC_2") (pintype "bidirectional"))
    )
    (net (code "68") (name "V+") (class "Default")
      (node (ref "C16") (pin "1") (pinfunction "1_1") (pintype "passive"))
      (node (ref "C27") (pin "+") (pinfunction "+_+") (pintype "passive"))
      (node (ref "INA219") (pin "1") (pinfunction "VIN+_1") (pintype "bidirectional"))
      (node (ref "PWR") (pin "1") (pinfunction "1_1") (pintype "passive"))
      (node (ref "R17") (pin "2") (pinfunction "2_2") (pintype "passive"))
      (node (ref "R34") (pin "2") (pinfunction "2_2") (pintype "passive"))
    )
    (net (code "69") (name "unconnected-(MPU6050-AUX_CL-Pad7)") (class "Default")
      (node (ref "MPU6050") (pin "7") (pinfunction "AUX_CL_7") (pintype "input"))
    )
    (net (code "70") (name "unconnected-(MPU6050-AUX_DA-Pad6)") (class "Default")
      (node (ref "MPU6050") (pin "6") (pinfunction "AUX_DA_6") (pintype "bidirectional"))
    )
    (net (code "71") (name "unconnected-(MPU6050-RESV-Pad19)") (class "Default")
      (node (ref "MPU6050") (pin "19") (pinfunction "RESV_19") (pintype "passive"))
    )
    (net (code "72") (name "unconnected-(MPU6050-RESV-Pad21)") (class "Default")
      (node (ref "MPU6050") (pin "21") (pinfunction "RESV_21") (pintype "passive"))
    )
    (net (code "73") (name "unconnected-(MPU6050-RESV-Pad22)") (class "Default")
      (node (ref "MPU6050") (pin "22") (pinfunction "RESV_22") (pintype "passive"))
    )
    (net (code "74") (name "unconnected-(PCA9533-LED3-Pad5)") (class "Default")
      (node (ref "PCA9533") (pin "5") (pinfunction "LED3_5") (pintype "bidirectional"))
    )
    (net (code "75") (name "unconnected-(RPI_ZERO-Pad2)") (class "Default")
      (node (ref "RPI_ZERO") (pin "2") (pinfunction "2_2") (pintype "passive"))
    )
    (net (code "76") (name "unconnected-(RPI_ZERO-Pad3)") (class "Default")
      (node (ref "RPI_ZERO") (pin "3") (pinfunction "3_3") (pintype "passive"))
    )
    (net (code "77") (name "unconnected-(RPI_ZERO-Pad4)") (class "Default")
      (node (ref "RPI_ZERO") (pin "4") (pinfunction "4_4") (pintype "passive"))
    )
    (net (code "78") (name "unconnected-(RPI_ZERO-Pad5)") (class "Default")
      (node (ref "RPI_ZERO") (pin "5") (pinfunction "5_5") (pintype "passive"))
    )
    (net (code "79") (name "unconnected-(RPI_ZERO-Pad6)") (class "Default")
      (node (ref "RPI_ZERO") (pin "6") (pinfunction "6_6") (pintype "passive"))
    )
    (net (code "80") (name "unconnected-(RPI_ZERO-Pad7)") (class "Default")
      (node (ref "RPI_ZERO") (pin "7") (pinfunction "7_7") (pintype "passive"))
    )
    (net (code "81") (name "unconnected-(RPI_ZERO-Pad9)") (class "Default")
      (node (ref "RPI_ZERO") (pin "9") (pinfunction "9_9") (pintype "passive"))
    )
    (net (code "82") (name "unconnected-(RPI_ZERO-Pad10)") (class "Default")
      (node (ref "RPI_ZERO") (pin "10") (pinfunction "10_10") (pintype "passive"))
    )
    (net (code "83") (name "unconnected-(RPI_ZERO-Pad11)") (class "Default")
      (node (ref "RPI_ZERO") (pin "11") (pinfunction "11_11") (pintype "passive"))
    )
    (net (code "84") (name "unconnected-(RPI_ZERO-Pad13)") (class "Default")
      (node (ref "RPI_ZERO") (pin "13") (pinfunction "13_13") (pintype "passive"))
    )
    (net (code "85") (name "unconnected-(RPI_ZERO-Pad14)") (class "Default")
      (node (ref "RPI_ZERO") (pin "14") (pinfunction "14_14") (pintype "passive"))
    )
    (net (code "86") (name "unconnected-(RPI_ZERO-Pad16)") (class "Default")
      (node (ref "RPI_ZERO") (pin "16") (pinfunction "16_16") (pintype "passive"))
    )
    (net (code "87") (name "unconnected-(RPI_ZERO-Pad17)") (class "Default")
      (node (ref "RPI_ZERO") (pin "17") (pinfunction "17_17") (pintype "passive"))
    )
    (net (code "88") (name "unconnected-(RPI_ZERO-Pad18)") (class "Default")
      (node (ref "RPI_ZERO") (pin "18") (pinfunction "18_18") (pintype "passive"))
    )
    (net (code "89") (name "unconnected-(RPI_ZERO-Pad19)") (class "Default")
      (node (ref "RPI_ZERO") (pin "19") (pinfunction "19_19") (pintype "passive"))
    )
    (net (code "90") (name "unconnected-(RPI_ZERO-Pad21)") (class "Default")
      (node (ref "RPI_ZERO") (pin "21") (pinfunction "21_21") (pintype "passive"))
    )
    (net (code "91") (name "unconnected-(RPI_ZERO-Pad23)") (class "Default")
      (node (ref "RPI_ZERO") (pin "23") (pinfunction "23_23") (pintype "passive"))
    )
    (net (code "92") (name "unconnected-(RPI_ZERO-Pad25)") (class "Default")
      (node (ref "RPI_ZERO") (pin "25") (pinfunction "25_25") (pintype "passive"))
    )
    (net (code "93") (name "unconnected-(RPI_ZERO-Pad27)") (class "Default")
      (node (ref "RPI_ZERO") (pin "27") (pinfunction "27_27") (pintype "passive"))
    )
    (net (code "94") (name "unconnected-(RPI_ZERO-Pad29)") (class "Default")
      (node (ref "RPI_ZERO") (pin "29") (pinfunction "29_29") (pintype "passive"))
    )
    (net (code "95") (name "unconnected-(RPI_ZERO-Pad30)") (class "Default")
      (node (ref "RPI_ZERO") (pin "30") (pinfunction "30_30") (pintype "passive"))
    )
    (net (code "96") (name "unconnected-(RPI_ZERO-Pad33)") (class "Default")
      (node (ref "RPI_ZERO") (pin "33") (pinfunction "33_33") (pintype "passive"))
    )
    (net (code "97") (name "unconnected-(RPI_ZERO-Pad35)") (class "Default")
      (node (ref "RPI_ZERO") (pin "35") (pinfunction "35_35") (pintype "passive"))
    )
    (net (code "98") (name "unconnected-(RPI_ZERO-Pad37)") (class "Default")
      (node (ref "RPI_ZERO") (pin "37") (pinfunction "37_37") (pintype "passive"))
    )
    (net (code "99") (name "unconnected-(RPI_ZERO-Pad39)") (class "Default")
      (node (ref "RPI_ZERO") (pin "39") (pinfunction "39_39") (pintype "passive"))
    )
    (net (code "100") (name "unconnected-(STM32F103CB-PA1-Pad11)") (class "Default")
      (node (ref "STM32F103CB") (pin "11") (pinfunction "PA1_11") (pintype "bidirectional"))
    )
    (net (code "101") (name "unconnected-(STM32F103CB-PA8-Pad29)") (class "Default")
      (node (ref "STM32F103CB") (pin "29") (pinfunction "PA8_29") (pintype "bidirectional"))
    )
    (net (code "102") (name "unconnected-(STM32F103CB-PA15-Pad38)") (class "Default")
      (node (ref "STM32F103CB") (pin "38") (pinfunction "PA15_38") (pintype "bidirectional"))
    )
    (net (code "103") (name "unconnected-(STM32F103CB-PB3-Pad39)") (class "Default")
      (node (ref "STM32F103CB") (pin "39") (pinfunction "PB3_39") (pintype "bidirectional"))
    )
    (net (code "104") (name "unconnected-(STM32F103CB-PB4-Pad40)") (class "Default")
      (node (ref "STM32F103CB") (pin "40") (pinfunction "PB4_40") (pintype "bidirectional"))
    )
    (net (code "105") (name "unconnected-(STM32F103CB-PB5-Pad41)") (class "Default")
      (node (ref "STM32F103CB") (pin "41") (pinfunction "PB5_41") (pintype "bidirectional"))
    )
    (net (code "106") (name "unconnected-(STM32F103CB-PB8-Pad45)") (class "Default")
      (node (ref "STM32F103CB") (pin "45") (pinfunction "PB8_45") (pintype "bidirectional"))
    )
    (net (code "107") (name "unconnected-(STM32F103CB-PB9-Pad46)") (class "Default")
      (node (ref "STM32F103CB") (pin "46") (pinfunction "PB9_46") (pintype "bidirectional"))
    )
    (net (code "108") (name "unconnected-(STM32F103CB-PB10-Pad21)") (class "Default")
      (node (ref "STM32F103CB") (pin "21") (pinfunction "PB10_21") (pintype "bidirectional"))
    )
    (net (code "109") (name "unconnected-(STM32F103CB-PB11-Pad22)") (class "Default")
      (node (ref "STM32F103CB") (pin "22") (pinfunction "PB11_22") (pintype "bidirectional"))
    )
    (net (code "110") (name "unconnected-(STM32F103CB-PB13-Pad26)") (class "Default")
      (node (ref "STM32F103CB") (pin "26") (pinfunction "PB13_26") (pintype "bidirectional"))
    )
    (net (code "111") (name "unconnected-(STM32F103CB-PC14-OSC32_IN-Pad3)") (class "Default")
      (node (ref "STM32F103CB") (pin "3") (pinfunction "PC14-OSC32_IN_3") (pintype "bidirectional"))
    )
    (net (code "112") (name "unconnected-(STM32F103CB-PC15-OSC32_OUT-Pad4)") (class "Default")
      (node (ref "STM32F103CB") (pin "4") (pinfunction "PC15-OSC32_OUT_4") (pintype "bidirectional"))
    )
  )
)
